# teemsyUp.net
KiCad netlist of a schematic drawn in EAGLE
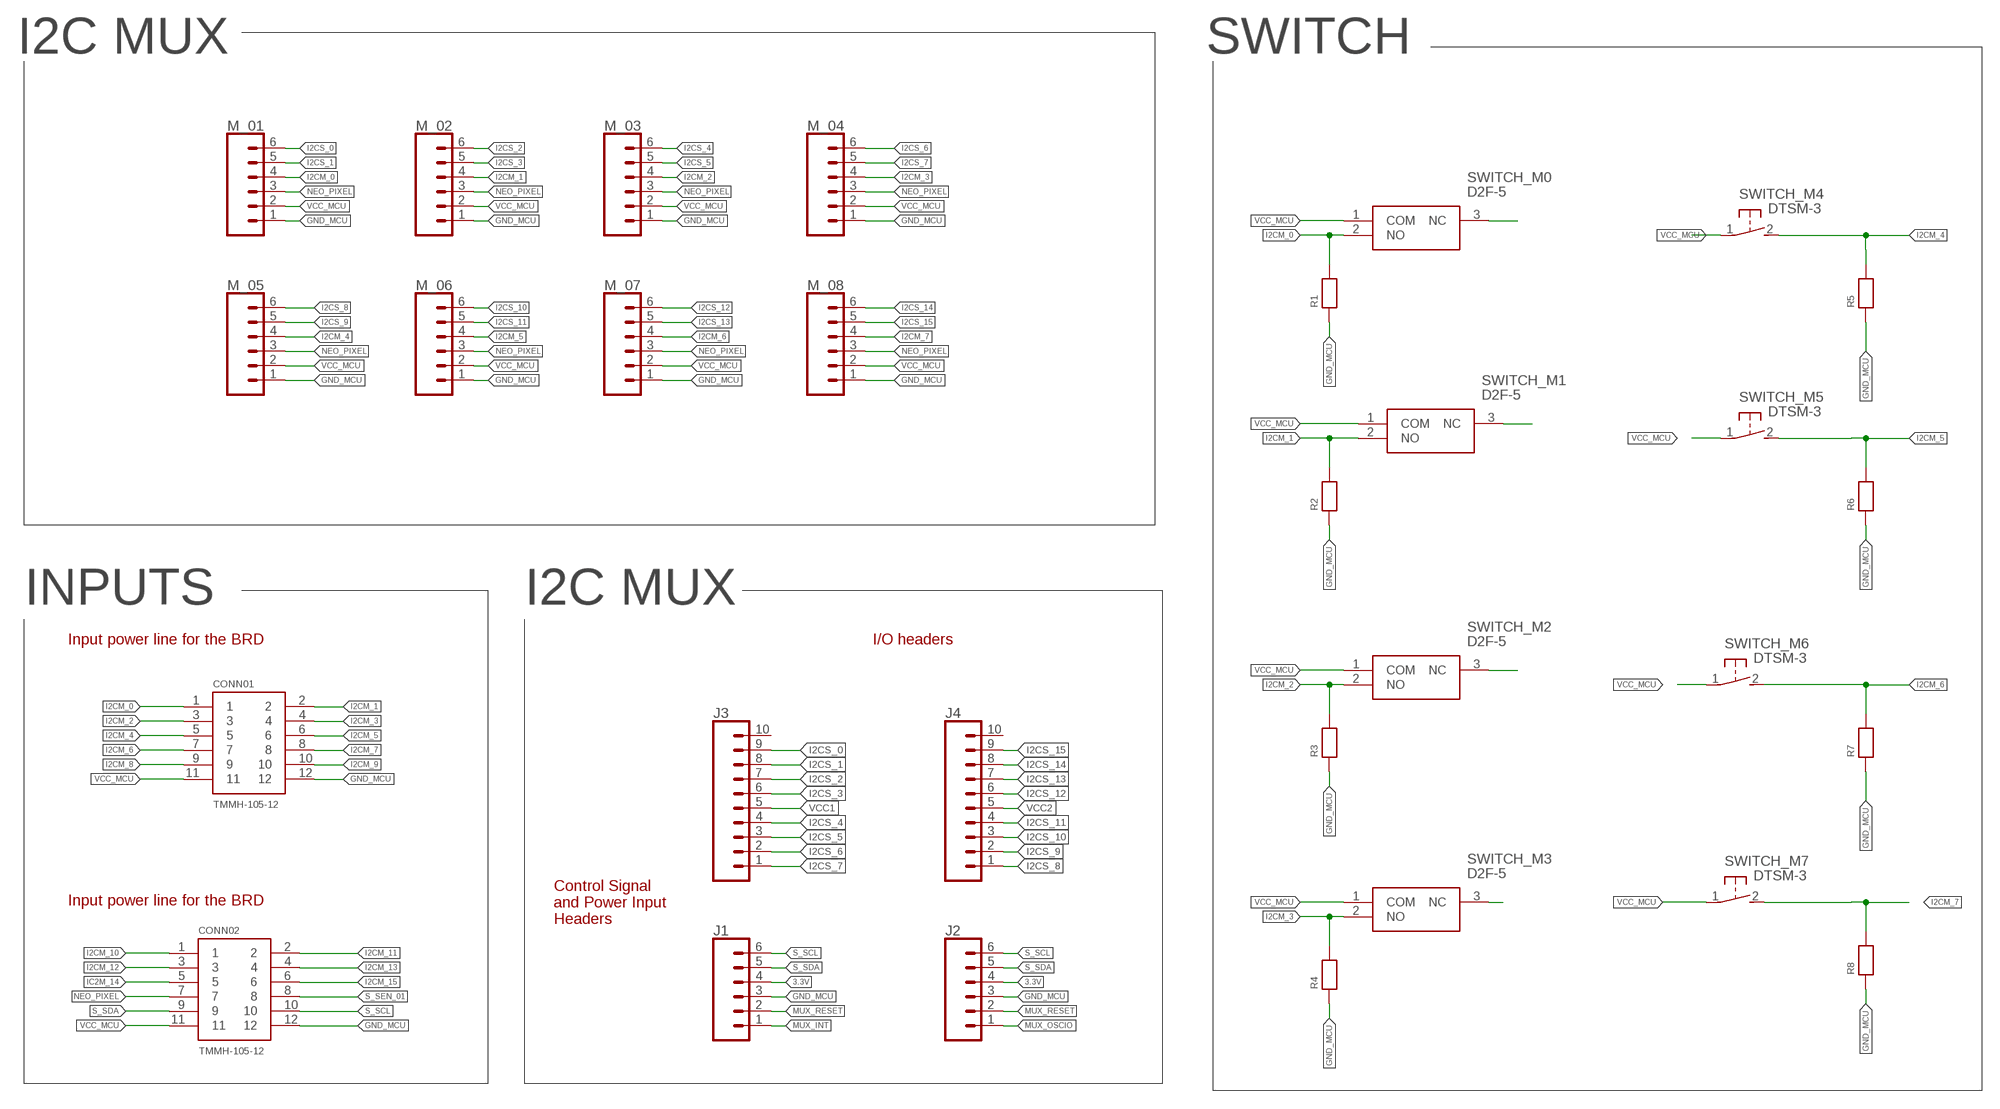
[diagram p0: schematic, sheet 1, part 1 of 2]
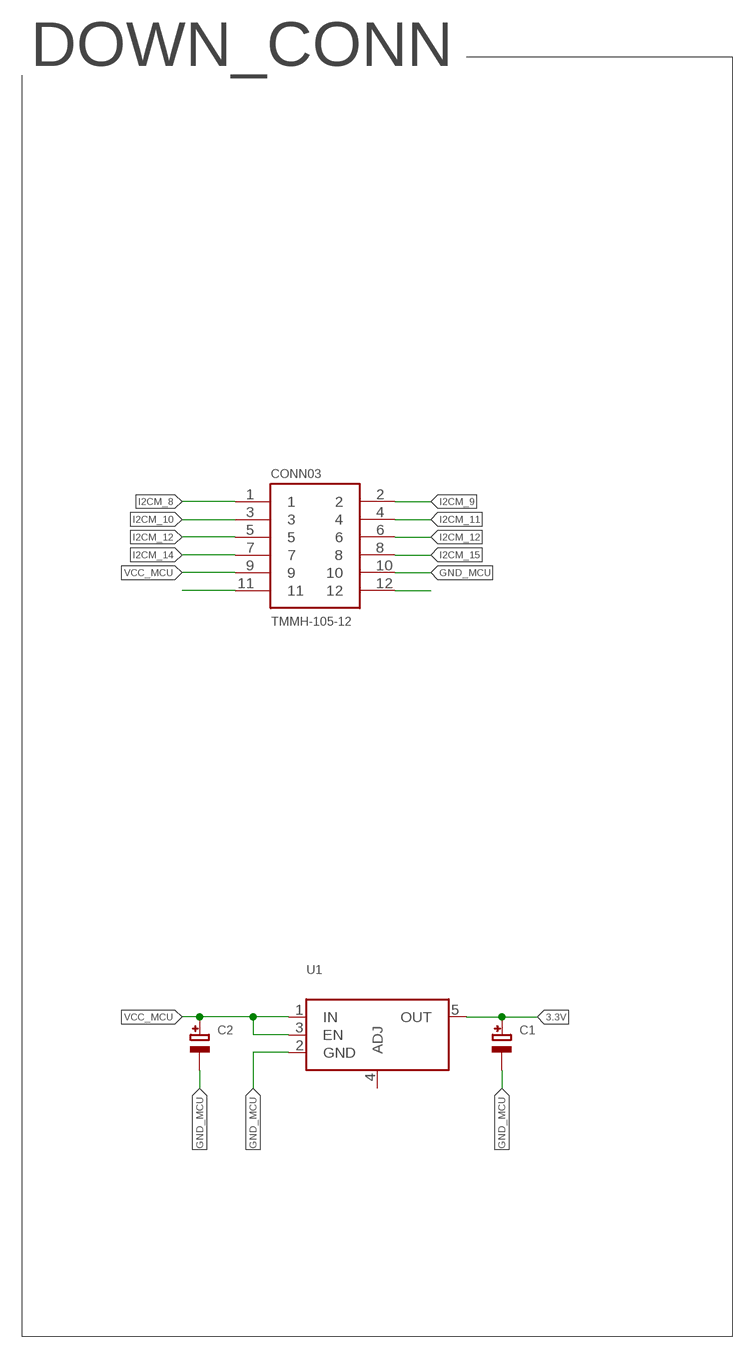
[diagram p1: schematic, sheet 1, part 2 of 2]

(export (version "E")
  (design (tool "Eeschema 10.0.6"))
  (components
    (comp (ref "C1")
      (value "CAP_TANTALUMA/3216_REFLOW")
      (footprint "eagle-import:EIA3216-18_A-R")
      (libsource (lib "eagle-import") (part "CAP_TANTALUMA/3216_REFLOW"))
    )
    (comp (ref "C2")
      (value "CAP_TANTALUMA/3216_REFLOW")
      (footprint "eagle-import:EIA3216-18_A-R")
      (libsource (lib "eagle-import") (part "CAP_TANTALUMA/3216_REFLOW"))
    )
    (comp (ref "CONN01")
      (value "TMMH-105-12")
      (footprint "eagle-import:TMMH-105-12")
      (libsource (lib "eagle-import") (part "TMMH-105-12"))
    )
    (comp (ref "CONN02")
      (value "TMMH-105-12")
      (footprint "eagle-import:TMMH-105-12")
      (libsource (lib "eagle-import") (part "TMMH-105-12"))
    )
    (comp (ref "CONN03")
      (value "TMMH-105-12")
      (footprint "eagle-import:TMMH-105-12")
      (libsource (lib "eagle-import") (part "TMMH-105-12"))
    )
    (comp (ref "J1")
      (value "CONN_06SMD_MALE")
      (footprint "eagle-import:1X06_SMD_MALE")
      (libsource (lib "eagle-import") (part "CONN_06SMD_MALE"))
    )
    (comp (ref "J2")
      (value "CONN_06SMD_MALE")
      (footprint "eagle-import:1X06_SMD_MALE")
      (libsource (lib "eagle-import") (part "CONN_06SMD_MALE"))
    )
    (comp (ref "J3")
      (value "CONN_10SMD_MALE")
      (footprint "eagle-import:1X10_SMD_MALE")
      (libsource (lib "eagle-import") (part "CONN_10SMD_MALE"))
    )
    (comp (ref "J4")
      (value "CONN_10SMD_MALE")
      (footprint "eagle-import:1X10_SMD_MALE")
      (libsource (lib "eagle-import") (part "CONN_10SMD_MALE"))
    )
    (comp (ref "M_01")
      (value "CONN_06SMD-1MM")
      (footprint "eagle-import:1X06-1MM")
      (libsource (lib "eagle-import") (part "CONN_06SMD-1MM"))
    )
    (comp (ref "M_02")
      (value "CONN_06SMD-1MM")
      (footprint "eagle-import:1X06-1MM")
      (libsource (lib "eagle-import") (part "CONN_06SMD-1MM"))
    )
    (comp (ref "M_03")
      (value "CONN_06SMD-1MM")
      (footprint "eagle-import:1X06-1MM")
      (libsource (lib "eagle-import") (part "CONN_06SMD-1MM"))
    )
    (comp (ref "M_04")
      (value "CONN_06SMD-1MM")
      (footprint "eagle-import:1X06-1MM")
      (libsource (lib "eagle-import") (part "CONN_06SMD-1MM"))
    )
    (comp (ref "M_05")
      (value "CONN_06SMD-1MM")
      (footprint "eagle-import:1X06-1MM")
      (libsource (lib "eagle-import") (part "CONN_06SMD-1MM"))
    )
    (comp (ref "M_06")
      (value "CONN_06SMD-1MM")
      (footprint "eagle-import:1X06-1MM")
      (libsource (lib "eagle-import") (part "CONN_06SMD-1MM"))
    )
    (comp (ref "M_07")
      (value "CONN_06SMD-1MM")
      (footprint "eagle-import:1X06-1MM")
      (libsource (lib "eagle-import") (part "CONN_06SMD-1MM"))
    )
    (comp (ref "M_08")
      (value "CONN_06SMD-1MM")
      (footprint "eagle-import:1X06-1MM")
      (libsource (lib "eagle-import") (part "CONN_06SMD-1MM"))
    )
    (comp (ref "R1")
      (value "RESISTOR1206")
      (footprint "eagle-import:1206")
      (libsource (lib "eagle-import") (part "RESISTOR1206"))
    )
    (comp (ref "R2")
      (value "RESISTOR1206")
      (footprint "eagle-import:1206")
      (libsource (lib "eagle-import") (part "RESISTOR1206"))
    )
    (comp (ref "R3")
      (value "RESISTOR1206")
      (footprint "eagle-import:1206")
      (libsource (lib "eagle-import") (part "RESISTOR1206"))
    )
    (comp (ref "R4")
      (value "RESISTOR1206")
      (footprint "eagle-import:1206")
      (libsource (lib "eagle-import") (part "RESISTOR1206"))
    )
    (comp (ref "R5")
      (value "RESISTOR1206")
      (footprint "eagle-import:1206")
      (libsource (lib "eagle-import") (part "RESISTOR1206"))
    )
    (comp (ref "R6")
      (value "RESISTOR1206")
      (footprint "eagle-import:1206")
      (libsource (lib "eagle-import") (part "RESISTOR1206"))
    )
    (comp (ref "R7")
      (value "RESISTOR1206")
      (footprint "eagle-import:1206")
      (libsource (lib "eagle-import") (part "RESISTOR1206"))
    )
    (comp (ref "R8")
      (value "RESISTOR1206")
      (footprint "eagle-import:1206")
      (libsource (lib "eagle-import") (part "RESISTOR1206"))
    )
    (comp (ref "SWITCH_M0")
      (value "D2F-5")
      (footprint "eagle-import:SHDR3W100P0X508_1X3_1280X580X5")
      (fields (field (name "MOUSER_PART_NUMBER") "653-D2F-5"))
      (libsource (lib "eagle-import") (part "D2F-5"))
    )
    (comp (ref "SWITCH_M1")
      (value "D2F-5")
      (footprint "eagle-import:SHDR3W100P0X508_1X3_1280X580X5")
      (fields (field (name "MOUSER_PART_NUMBER") "653-D2F-5"))
      (libsource (lib "eagle-import") (part "D2F-5"))
    )
    (comp (ref "SWITCH_M2")
      (value "D2F-5")
      (footprint "eagle-import:SHDR3W100P0X508_1X3_1280X580X5")
      (fields (field (name "MOUSER_PART_NUMBER") "653-D2F-5"))
      (libsource (lib "eagle-import") (part "D2F-5"))
    )
    (comp (ref "SWITCH_M3")
      (value "D2F-5")
      (footprint "eagle-import:SHDR3W100P0X508_1X3_1280X580X5")
      (fields (field (name "MOUSER_PART_NUMBER") "653-D2F-5"))
      (libsource (lib "eagle-import") (part "D2F-5"))
    )
    (comp (ref "SWITCH_M4")
      (value "DTSM-3")
      (footprint "eagle-import:DTSM-3")
      (libsource (lib "eagle-import") (part "DTSM-3"))
    )
    (comp (ref "SWITCH_M5")
      (value "DTSM-3")
      (footprint "eagle-import:DTSM-3")
      (libsource (lib "eagle-import") (part "DTSM-3"))
    )
    (comp (ref "SWITCH_M6")
      (value "DTSM-3")
      (footprint "eagle-import:DTSM-3")
      (libsource (lib "eagle-import") (part "DTSM-3"))
    )
    (comp (ref "SWITCH_M7")
      (value "DTSM-3")
      (footprint "eagle-import:DTSM-3")
      (libsource (lib "eagle-import") (part "DTSM-3"))
    )
    (comp (ref "U1")
      (value "ADP1712")
      (footprint "eagle-import:SOT23-5")
      (libsource (lib "eagle-import") (part "ADP1712"))
    )
  )
  (nets
    (net (code "1") (name "3.3V") (class "Default")
      (node (ref "C1") (pin "+") (pinfunction "+_+") (pintype "passive"))
      (node (ref "J1") (pin "4") (pinfunction "4_4") (pintype "passive"))
      (node (ref "J2") (pin "4") (pinfunction "4_4") (pintype "passive"))
      (node (ref "U1") (pin "5") (pinfunction "OUT_5") (pintype "bidirectional"))
    )
    (net (code "2") (name "GND_MCU") (class "Default")
      (node (ref "C1") (pin "-") (pinfunction "-_-") (pintype "passive"))
      (node (ref "C2") (pin "-") (pinfunction "-_-") (pintype "passive"))
      (node (ref "CONN01") (pin "12") (pinfunction "12_12") (pintype "bidirectional"))
      (node (ref "CONN02") (pin "12") (pinfunction "12_12") (pintype "bidirectional"))
      (node (ref "CONN03") (pin "10") (pinfunction "10_10") (pintype "bidirectional"))
      (node (ref "J1") (pin "3") (pinfunction "3_3") (pintype "passive"))
      (node (ref "J2") (pin "3") (pinfunction "3_3") (pintype "passive"))
      (node (ref "M_01") (pin "1") (pinfunction "1_1") (pintype "passive"))
      (node (ref "M_02") (pin "1") (pinfunction "1_1") (pintype "passive"))
      (node (ref "M_03") (pin "1") (pinfunction "1_1") (pintype "passive"))
      (node (ref "M_04") (pin "1") (pinfunction "1_1") (pintype "passive"))
      (node (ref "M_05") (pin "1") (pinfunction "1_1") (pintype "passive"))
      (node (ref "M_06") (pin "1") (pinfunction "1_1") (pintype "passive"))
      (node (ref "M_07") (pin "1") (pinfunction "1_1") (pintype "passive"))
      (node (ref "M_08") (pin "1") (pinfunction "1_1") (pintype "passive"))
      (node (ref "R1") (pin "1") (pinfunction "1_1") (pintype "passive"))
      (node (ref "R2") (pin "1") (pinfunction "1_1") (pintype "passive"))
      (node (ref "R3") (pin "1") (pinfunction "1_1") (pintype "passive"))
      (node (ref "R4") (pin "1") (pinfunction "1_1") (pintype "passive"))
      (node (ref "R5") (pin "1") (pinfunction "1_1") (pintype "passive"))
      (node (ref "R6") (pin "1") (pinfunction "1_1") (pintype "passive"))
      (node (ref "R7") (pin "1") (pinfunction "1_1") (pintype "passive"))
      (node (ref "R8") (pin "1") (pinfunction "1_1") (pintype "passive"))
      (node (ref "U1") (pin "2") (pinfunction "GND_2") (pintype "bidirectional"))
    )
    (net (code "3") (name "I2CM_0") (class "Default")
      (node (ref "CONN01") (pin "1") (pinfunction "1_1") (pintype "bidirectional"))
      (node (ref "M_01") (pin "4") (pinfunction "4_4") (pintype "passive"))
      (node (ref "R1") (pin "2") (pinfunction "2_2") (pintype "passive"))
      (node (ref "SWITCH_M0") (pin "2") (pinfunction "NO_2") (pintype "bidirectional"))
    )
    (net (code "4") (name "I2CM_1") (class "Default")
      (node (ref "CONN01") (pin "2") (pinfunction "2_2") (pintype "bidirectional"))
      (node (ref "M_02") (pin "4") (pinfunction "4_4") (pintype "passive"))
      (node (ref "R2") (pin "2") (pinfunction "2_2") (pintype "passive"))
      (node (ref "SWITCH_M1") (pin "2") (pinfunction "NO_2") (pintype "bidirectional"))
    )
    (net (code "5") (name "I2CM_2") (class "Default")
      (node (ref "CONN01") (pin "3") (pinfunction "3_3") (pintype "bidirectional"))
      (node (ref "M_03") (pin "4") (pinfunction "4_4") (pintype "passive"))
      (node (ref "R3") (pin "2") (pinfunction "2_2") (pintype "passive"))
      (node (ref "SWITCH_M2") (pin "2") (pinfunction "NO_2") (pintype "bidirectional"))
    )
    (net (code "6") (name "I2CM_3") (class "Default")
      (node (ref "CONN01") (pin "4") (pinfunction "4_4") (pintype "bidirectional"))
      (node (ref "M_04") (pin "4") (pinfunction "4_4") (pintype "passive"))
      (node (ref "R4") (pin "2") (pinfunction "2_2") (pintype "passive"))
      (node (ref "SWITCH_M3") (pin "2") (pinfunction "NO_2") (pintype "bidirectional"))
    )
    (net (code "7") (name "I2CM_4") (class "Default")
      (node (ref "CONN01") (pin "5") (pinfunction "5_5") (pintype "bidirectional"))
      (node (ref "M_05") (pin "4") (pinfunction "4_4") (pintype "passive"))
      (node (ref "R5") (pin "2") (pinfunction "2_2") (pintype "passive"))
      (node (ref "SWITCH_M4") (pin "2") (pinfunction "2_2") (pintype "passive"))
    )
    (net (code "8") (name "I2CM_5") (class "Default")
      (node (ref "CONN01") (pin "6") (pinfunction "6_6") (pintype "bidirectional"))
      (node (ref "M_06") (pin "4") (pinfunction "4_4") (pintype "passive"))
      (node (ref "R6") (pin "2") (pinfunction "2_2") (pintype "passive"))
      (node (ref "SWITCH_M5") (pin "2") (pinfunction "2_2") (pintype "passive"))
    )
    (net (code "9") (name "I2CM_6") (class "Default")
      (node (ref "CONN01") (pin "7") (pinfunction "7_7") (pintype "bidirectional"))
      (node (ref "M_07") (pin "4") (pinfunction "4_4") (pintype "passive"))
      (node (ref "R7") (pin "2") (pinfunction "2_2") (pintype "passive"))
      (node (ref "SWITCH_M6") (pin "2") (pinfunction "2_2") (pintype "passive"))
    )
    (net (code "10") (name "I2CM_7") (class "Default")
      (node (ref "CONN01") (pin "8") (pinfunction "8_8") (pintype "bidirectional"))
      (node (ref "M_08") (pin "4") (pinfunction "4_4") (pintype "passive"))
      (node (ref "R8") (pin "2") (pinfunction "2_2") (pintype "passive"))
      (node (ref "SWITCH_M7") (pin "2") (pinfunction "2_2") (pintype "passive"))
    )
    (net (code "11") (name "I2CM_8") (class "Default")
      (node (ref "CONN01") (pin "9") (pinfunction "9_9") (pintype "bidirectional"))
      (node (ref "CONN03") (pin "1") (pinfunction "1_1") (pintype "bidirectional"))
    )
    (net (code "12") (name "I2CM_9") (class "Default")
      (node (ref "CONN01") (pin "10") (pinfunction "10_10") (pintype "bidirectional"))
      (node (ref "CONN03") (pin "2") (pinfunction "2_2") (pintype "bidirectional"))
    )
    (net (code "13") (name "I2CM_10") (class "Default")
      (node (ref "CONN02") (pin "1") (pinfunction "1_1") (pintype "bidirectional"))
      (node (ref "CONN03") (pin "3") (pinfunction "3_3") (pintype "bidirectional"))
    )
    (net (code "14") (name "I2CM_11") (class "Default")
      (node (ref "CONN02") (pin "2") (pinfunction "2_2") (pintype "bidirectional"))
      (node (ref "CONN03") (pin "4") (pinfunction "4_4") (pintype "bidirectional"))
    )
    (net (code "15") (name "I2CM_12") (class "Default")
      (node (ref "CONN02") (pin "3") (pinfunction "3_3") (pintype "bidirectional"))
      (node (ref "CONN03") (pin "5") (pinfunction "5_5") (pintype "bidirectional"))
      (node (ref "CONN03") (pin "6") (pinfunction "6_6") (pintype "bidirectional"))
    )
    (net (code "16") (name "I2CM_13") (class "Default")
      (node (ref "CONN02") (pin "4") (pinfunction "4_4") (pintype "bidirectional"))
    )
    (net (code "17") (name "I2CM_14") (class "Default")
      (node (ref "CONN03") (pin "7") (pinfunction "7_7") (pintype "bidirectional"))
    )
    (net (code "18") (name "I2CM_15") (class "Default")
      (node (ref "CONN02") (pin "6") (pinfunction "6_6") (pintype "bidirectional"))
      (node (ref "CONN03") (pin "8") (pinfunction "8_8") (pintype "bidirectional"))
    )
    (net (code "19") (name "I2CS_0") (class "Default")
      (node (ref "J3") (pin "9") (pinfunction "9_9") (pintype "passive"))
      (node (ref "M_01") (pin "6") (pinfunction "6_6") (pintype "passive"))
    )
    (net (code "20") (name "I2CS_1") (class "Default")
      (node (ref "J3") (pin "8") (pinfunction "8_8") (pintype "passive"))
      (node (ref "M_01") (pin "5") (pinfunction "5_5") (pintype "passive"))
    )
    (net (code "21") (name "I2CS_2") (class "Default")
      (node (ref "J3") (pin "7") (pinfunction "7_7") (pintype "passive"))
      (node (ref "M_02") (pin "6") (pinfunction "6_6") (pintype "passive"))
    )
    (net (code "22") (name "I2CS_3") (class "Default")
      (node (ref "J3") (pin "6") (pinfunction "6_6") (pintype "passive"))
      (node (ref "M_02") (pin "5") (pinfunction "5_5") (pintype "passive"))
    )
    (net (code "23") (name "I2CS_4") (class "Default")
      (node (ref "J3") (pin "4") (pinfunction "4_4") (pintype "passive"))
      (node (ref "M_03") (pin "6") (pinfunction "6_6") (pintype "passive"))
    )
    (net (code "24") (name "I2CS_5") (class "Default")
      (node (ref "J3") (pin "3") (pinfunction "3_3") (pintype "passive"))
      (node (ref "M_03") (pin "5") (pinfunction "5_5") (pintype "passive"))
    )
    (net (code "25") (name "I2CS_6") (class "Default")
      (node (ref "J3") (pin "2") (pinfunction "2_2") (pintype "passive"))
      (node (ref "M_04") (pin "6") (pinfunction "6_6") (pintype "passive"))
    )
    (net (code "26") (name "I2CS_7") (class "Default")
      (node (ref "J3") (pin "1") (pinfunction "1_1") (pintype "passive"))
      (node (ref "M_04") (pin "5") (pinfunction "5_5") (pintype "passive"))
    )
    (net (code "27") (name "I2CS_8") (class "Default")
      (node (ref "J4") (pin "1") (pinfunction "1_1") (pintype "passive"))
      (node (ref "M_05") (pin "6") (pinfunction "6_6") (pintype "passive"))
    )
    (net (code "28") (name "I2CS_9") (class "Default")
      (node (ref "J4") (pin "2") (pinfunction "2_2") (pintype "passive"))
      (node (ref "M_05") (pin "5") (pinfunction "5_5") (pintype "passive"))
    )
    (net (code "29") (name "I2CS_10") (class "Default")
      (node (ref "J4") (pin "3") (pinfunction "3_3") (pintype "passive"))
      (node (ref "M_06") (pin "6") (pinfunction "6_6") (pintype "passive"))
    )
    (net (code "30") (name "I2CS_11") (class "Default")
      (node (ref "J4") (pin "4") (pinfunction "4_4") (pintype "passive"))
      (node (ref "M_06") (pin "5") (pinfunction "5_5") (pintype "passive"))
    )
    (net (code "31") (name "I2CS_12") (class "Default")
      (node (ref "J4") (pin "6") (pinfunction "6_6") (pintype "passive"))
      (node (ref "M_07") (pin "6") (pinfunction "6_6") (pintype "passive"))
    )
    (net (code "32") (name "I2CS_13") (class "Default")
      (node (ref "J4") (pin "7") (pinfunction "7_7") (pintype "passive"))
      (node (ref "M_07") (pin "5") (pinfunction "5_5") (pintype "passive"))
    )
    (net (code "33") (name "I2CS_14") (class "Default")
      (node (ref "J4") (pin "8") (pinfunction "8_8") (pintype "passive"))
      (node (ref "M_08") (pin "6") (pinfunction "6_6") (pintype "passive"))
    )
    (net (code "34") (name "I2CS_15") (class "Default")
      (node (ref "J4") (pin "9") (pinfunction "9_9") (pintype "passive"))
      (node (ref "M_08") (pin "5") (pinfunction "5_5") (pintype "passive"))
    )
    (net (code "35") (name "IC2M_14") (class "Default")
      (node (ref "CONN02") (pin "5") (pinfunction "5_5") (pintype "bidirectional"))
    )
    (net (code "36") (name "MUX_INT") (class "Default")
      (node (ref "J1") (pin "1") (pinfunction "1_1") (pintype "passive"))
    )
    (net (code "37") (name "MUX_OSCIO") (class "Default")
      (node (ref "J2") (pin "1") (pinfunction "1_1") (pintype "passive"))
    )
    (net (code "38") (name "MUX_RESET") (class "Default")
      (node (ref "J1") (pin "2") (pinfunction "2_2") (pintype "passive"))
      (node (ref "J2") (pin "2") (pinfunction "2_2") (pintype "passive"))
    )
    (net (code "39") (name "NEO_PIXEL") (class "Default")
      (node (ref "CONN02") (pin "7") (pinfunction "7_7") (pintype "bidirectional"))
      (node (ref "M_01") (pin "3") (pinfunction "3_3") (pintype "passive"))
      (node (ref "M_02") (pin "3") (pinfunction "3_3") (pintype "passive"))
      (node (ref "M_03") (pin "3") (pinfunction "3_3") (pintype "passive"))
      (node (ref "M_04") (pin "3") (pinfunction "3_3") (pintype "passive"))
      (node (ref "M_05") (pin "3") (pinfunction "3_3") (pintype "passive"))
      (node (ref "M_06") (pin "3") (pinfunction "3_3") (pintype "passive"))
      (node (ref "M_07") (pin "3") (pinfunction "3_3") (pintype "passive"))
      (node (ref "M_08") (pin "3") (pinfunction "3_3") (pintype "passive"))
    )
    (net (code "40") (name "S_SCL") (class "Default")
      (node (ref "CONN02") (pin "10") (pinfunction "10_10") (pintype "bidirectional"))
      (node (ref "J1") (pin "6") (pinfunction "6_6") (pintype "passive"))
      (node (ref "J2") (pin "6") (pinfunction "6_6") (pintype "passive"))
    )
    (net (code "41") (name "S_SDA") (class "Default")
      (node (ref "CONN02") (pin "9") (pinfunction "9_9") (pintype "bidirectional"))
      (node (ref "J1") (pin "5") (pinfunction "5_5") (pintype "passive"))
      (node (ref "J2") (pin "5") (pinfunction "5_5") (pintype "passive"))
    )
    (net (code "42") (name "S_SEN_01") (class "Default")
      (node (ref "CONN02") (pin "8") (pinfunction "8_8") (pintype "bidirectional"))
    )
    (net (code "43") (name "VCC1") (class "Default")
      (node (ref "J3") (pin "5") (pinfunction "5_5") (pintype "passive"))
    )
    (net (code "44") (name "VCC2") (class "Default")
      (node (ref "J4") (pin "5") (pinfunction "5_5") (pintype "passive"))
    )
    (net (code "45") (name "VCC_MCU") (class "Default")
      (node (ref "C2") (pin "+") (pinfunction "+_+") (pintype "passive"))
      (node (ref "CONN01") (pin "11") (pinfunction "11_11") (pintype "bidirectional"))
      (node (ref "CONN02") (pin "11") (pinfunction "11_11") (pintype "bidirectional"))
      (node (ref "CONN03") (pin "9") (pinfunction "9_9") (pintype "bidirectional"))
      (node (ref "M_01") (pin "2") (pinfunction "2_2") (pintype "passive"))
      (node (ref "M_02") (pin "2") (pinfunction "2_2") (pintype "passive"))
      (node (ref "M_03") (pin "2") (pinfunction "2_2") (pintype "passive"))
      (node (ref "M_04") (pin "2") (pinfunction "2_2") (pintype "passive"))
      (node (ref "M_05") (pin "2") (pinfunction "2_2") (pintype "passive"))
      (node (ref "M_06") (pin "2") (pinfunction "2_2") (pintype "passive"))
      (node (ref "M_07") (pin "2") (pinfunction "2_2") (pintype "passive"))
      (node (ref "M_08") (pin "2") (pinfunction "2_2") (pintype "passive"))
      (node (ref "SWITCH_M0") (pin "1") (pinfunction "COM_1") (pintype "bidirectional"))
      (node (ref "SWITCH_M1") (pin "1") (pinfunction "COM_1") (pintype "bidirectional"))
      (node (ref "SWITCH_M2") (pin "1") (pinfunction "COM_1") (pintype "bidirectional"))
      (node (ref "SWITCH_M3") (pin "1") (pinfunction "COM_1") (pintype "bidirectional"))
      (node (ref "SWITCH_M4") (pin "1") (pinfunction "1_1") (pintype "passive"))
      (node (ref "SWITCH_M5") (pin "1") (pinfunction "1_1") (pintype "passive"))
      (node (ref "SWITCH_M6") (pin "1") (pinfunction "1_1") (pintype "passive"))
      (node (ref "SWITCH_M7") (pin "1") (pinfunction "1_1") (pintype "passive"))
      (node (ref "U1") (pin "1") (pinfunction "IN_1") (pintype "bidirectional"))
      (node (ref "U1") (pin "3") (pinfunction "EN_3") (pintype "bidirectional"))
    )
    (net (code "46") (name "unconnected-(CONN03-Pad11)") (class "Default")
      (node (ref "CONN03") (pin "11") (pinfunction "11_11") (pintype "bidirectional"))
    )
    (net (code "47") (name "unconnected-(CONN03-Pad12)") (class "Default")
      (node (ref "CONN03") (pin "12") (pinfunction "12_12") (pintype "bidirectional"))
    )
    (net (code "48") (name "unconnected-(J3-Pad10)") (class "Default")
      (node (ref "J3") (pin "10") (pinfunction "10_10") (pintype "passive"))
    )
    (net (code "49") (name "unconnected-(J4-Pad10)") (class "Default")
      (node (ref "J4") (pin "10") (pinfunction "10_10") (pintype "passive"))
    )
    (net (code "50") (name "unconnected-(SWITCH_M0-NC-Pad3)") (class "Default")
      (node (ref "SWITCH_M0") (pin "3") (pinfunction "NC_3") (pintype "no_connect"))
    )
    (net (code "51") (name "unconnected-(SWITCH_M1-NC-Pad3)") (class "Default")
      (node (ref "SWITCH_M1") (pin "3") (pinfunction "NC_3") (pintype "no_connect"))
    )
    (net (code "52") (name "unconnected-(SWITCH_M2-NC-Pad3)") (class "Default")
      (node (ref "SWITCH_M2") (pin "3") (pinfunction "NC_3") (pintype "no_connect"))
    )
    (net (code "53") (name "unconnected-(SWITCH_M3-NC-Pad3)") (class "Default")
      (node (ref "SWITCH_M3") (pin "3") (pinfunction "NC_3") (pintype "no_connect"))
    )
    (net (code "54") (name "unconnected-(U1-ADJ-Pad4)") (class "Default")
      (node (ref "U1") (pin "4") (pinfunction "ADJ_4") (pintype "bidirectional"))
    )
  )
)
